# FOC_Explore.net
KiCad netlist of a schematic drawn in EasyEDA Pro
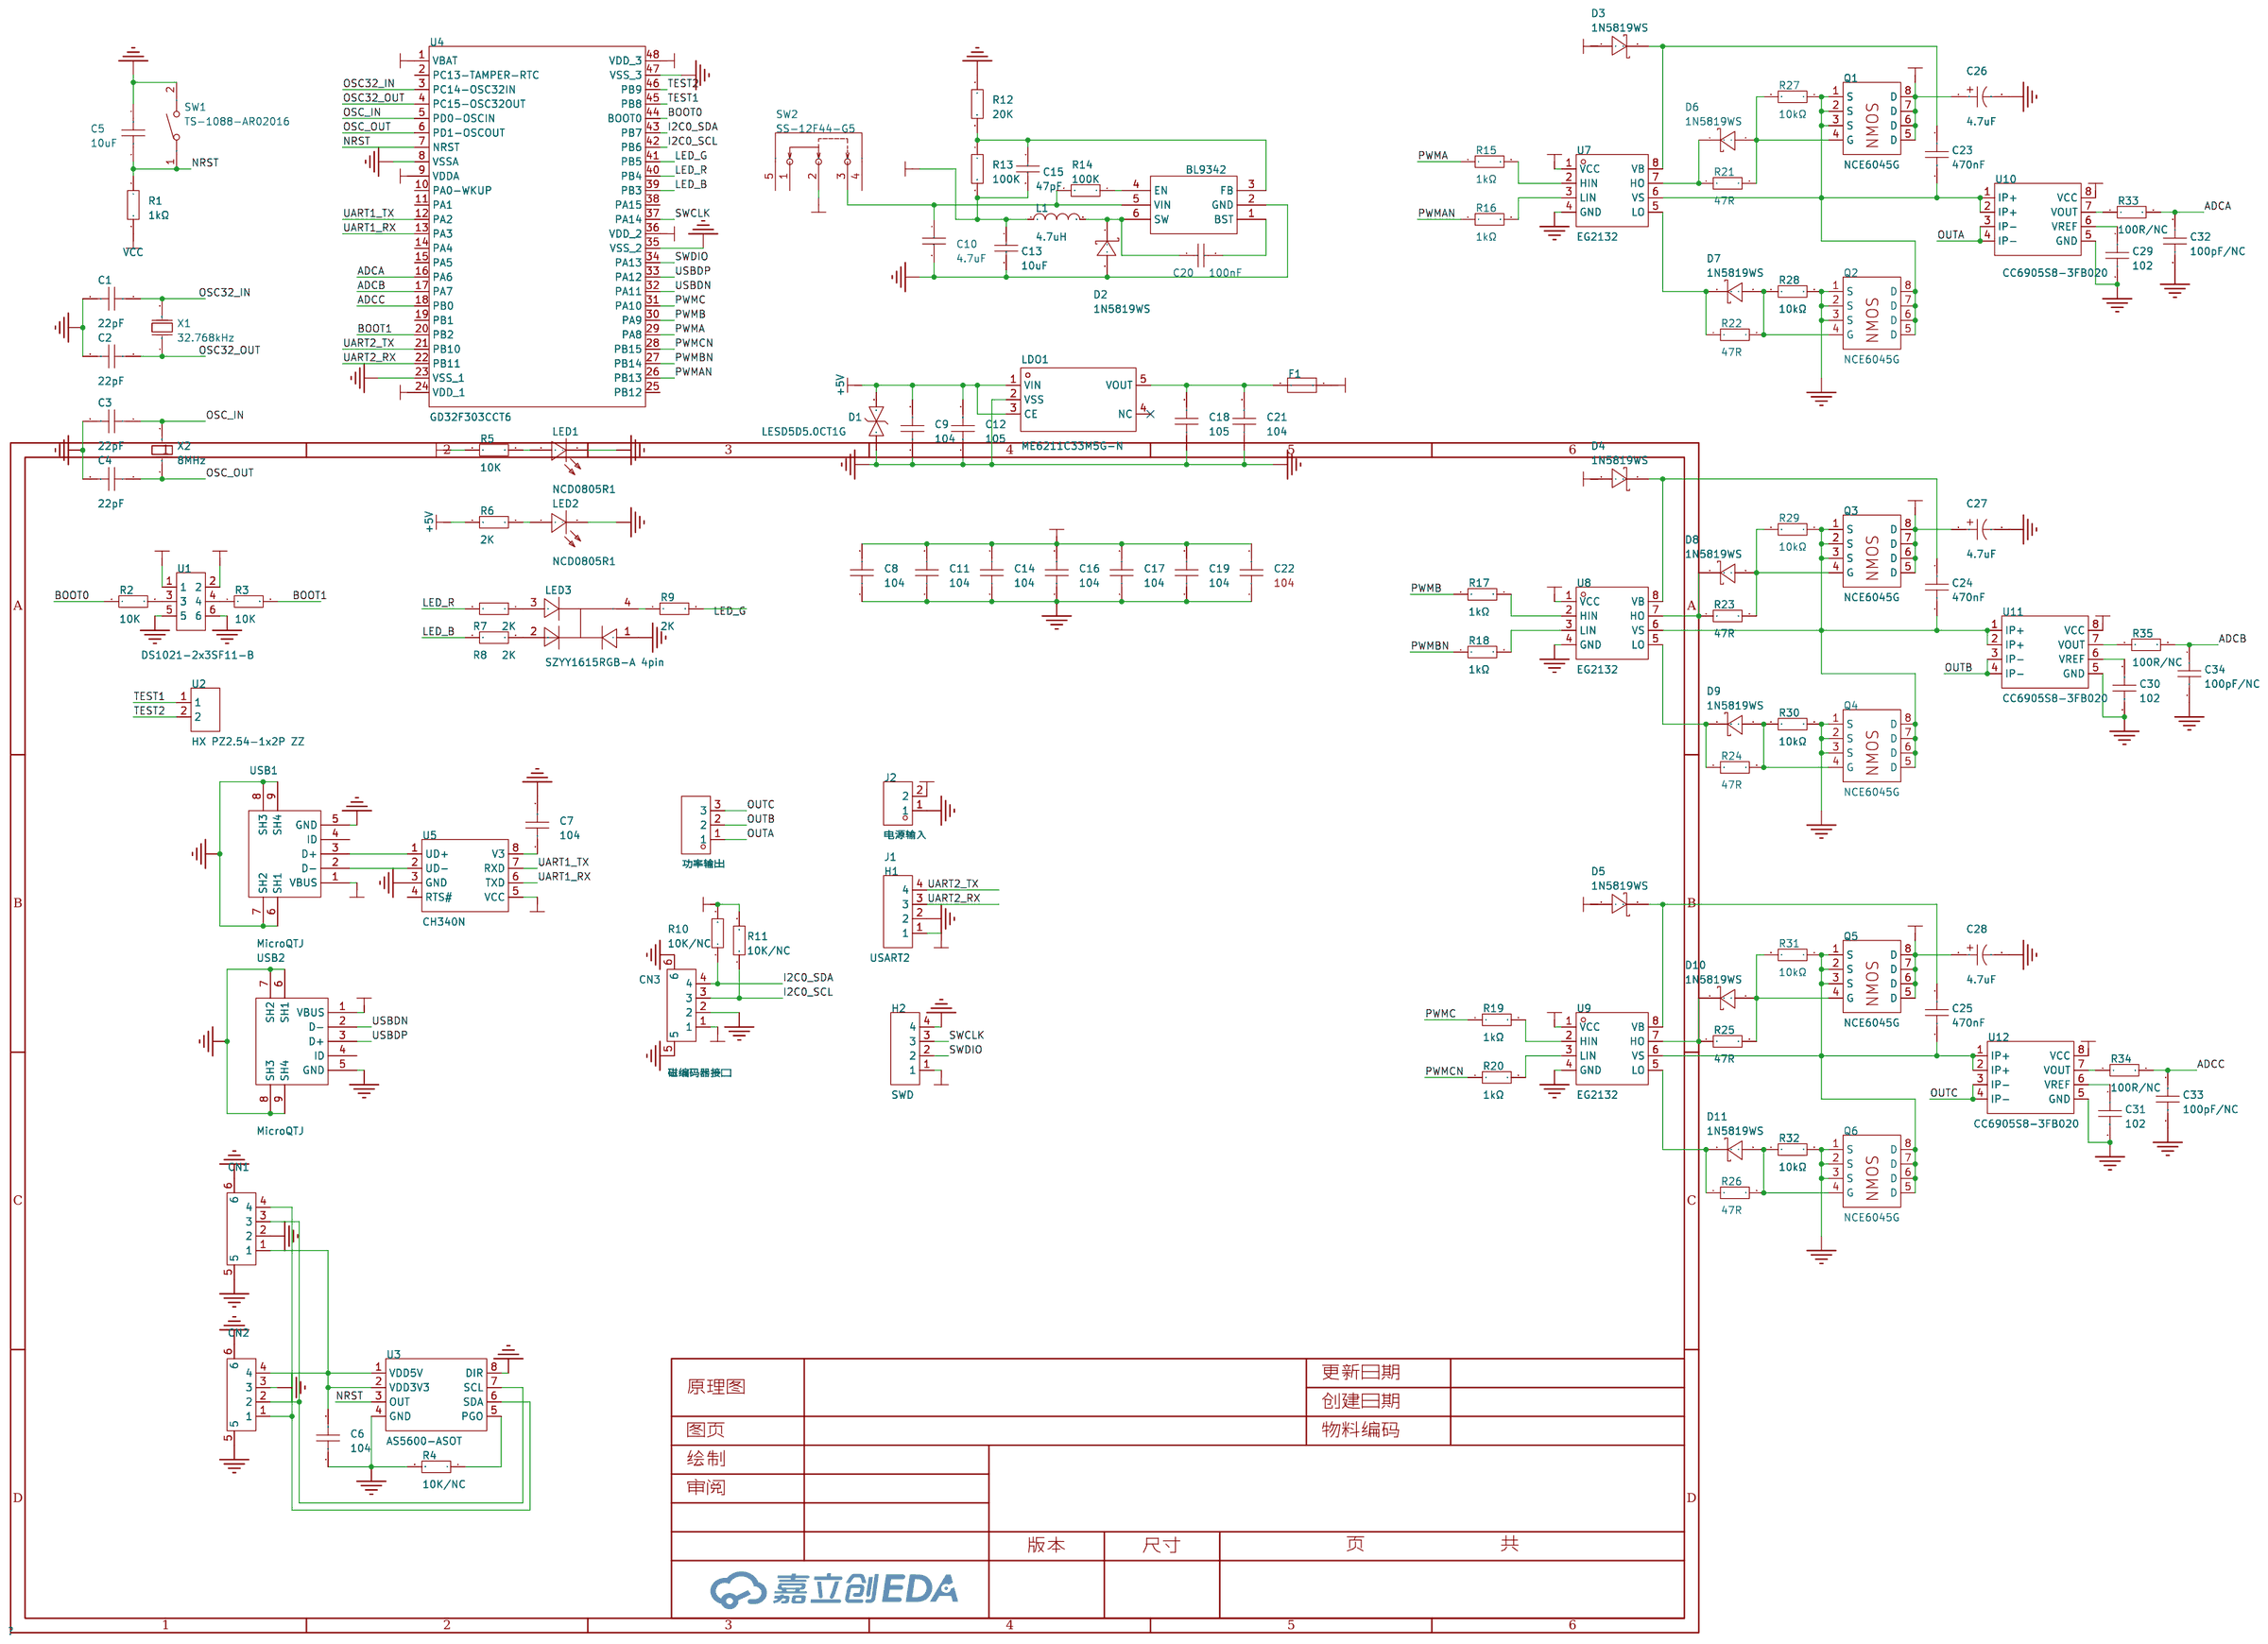
[diagram p0: schematic sheet]

(export (version "E")
  (design (tool "Eeschema 10.0.6"))
  (components
    (comp (ref "C1")
      (value "22pF")
      (footprint "easyedapro:C0805")
      (fields (field (name "Manufacturer") "FH(风华)"))
      (libsource (lib "easyedapro") (part "0805DS106K250NT"))
    )
    (comp (ref "C2")
      (value "22pF")
      (footprint "easyedapro:C0805")
      (fields (field (name "Manufacturer") "FH(风华)"))
      (libsource (lib "easyedapro") (part "0805DS106K250NT"))
    )
    (comp (ref "C3")
      (value "22pF")
      (footprint "easyedapro:C0805")
      (fields (field (name "Manufacturer") "FH(风华)"))
      (libsource (lib "easyedapro") (part "0805DS106K250NT"))
    )
    (comp (ref "C4")
      (value "22pF")
      (footprint "easyedapro:C0805")
      (fields (field (name "Manufacturer") "FH(风华)"))
      (libsource (lib "easyedapro") (part "0805DS106K250NT"))
    )
    (comp (ref "C5")
      (value "10uF")
      (footprint "easyedapro:C0805")
      (fields (field (name "Manufacturer") "FH(风华)"))
      (libsource (lib "easyedapro") (part "0805DS106K250NT"))
    )
    (comp (ref "C6")
      (value "104")
      (footprint "easyedapro:C0603")
      (fields (field (name "Manufacturer") "FH(风华)"))
      (libsource (lib "easyedapro") (part "0603DS106M160NT"))
    )
    (comp (ref "C7")
      (value "104")
      (footprint "easyedapro:C0603")
      (fields (field (name "Manufacturer") "FH(风华)"))
      (libsource (lib "easyedapro") (part "0603DS106M160NT"))
    )
    (comp (ref "C8")
      (value "104")
      (footprint "easyedapro:C0603")
      (fields (field (name "Manufacturer") "FH(风华)"))
      (libsource (lib "easyedapro") (part "0603DS106M160NT"))
    )
    (comp (ref "C9")
      (value "104")
      (footprint "easyedapro:C0603")
      (fields (field (name "Manufacturer") "FH(风华)"))
      (libsource (lib "easyedapro") (part "0603DS106M160NT"))
    )
    (comp (ref "C10")
      (value "4.7uF")
      (footprint "easyedapro:C0603")
      (fields
        (field (name "Manufacturer Part") "CL10C330JB8NNNC")
        (field (name "Manufacturer") "SAMSUNG(三星)")
      )
      (libsource (lib "easyedapro") (part "33pF"))
    )
    (comp (ref "C11")
      (value "104")
      (footprint "easyedapro:C0603")
      (fields (field (name "Manufacturer") "FH(风华)"))
      (libsource (lib "easyedapro") (part "0603DS106M160NT"))
    )
    (comp (ref "C12")
      (value "105")
      (footprint "easyedapro:C0603")
      (fields (field (name "Manufacturer") "FH(风华)"))
      (libsource (lib "easyedapro") (part "0603DS106M160NT"))
    )
    (comp (ref "C13")
      (value "10uF")
      (footprint "easyedapro:C0603")
      (fields (field (name "Manufacturer Part") "0603B104K500NT") (field (name "Manufacturer") "FH(风华)"))
      (libsource (lib "easyedapro") (part "100nF"))
    )
    (comp (ref "C14")
      (value "104")
      (footprint "easyedapro:C0603")
      (fields (field (name "Manufacturer") "FH(风华)"))
      (libsource (lib "easyedapro") (part "0603DS106M160NT"))
    )
    (comp (ref "C15")
      (value "47pF")
      (footprint "easyedapro:C0603")
      (fields (field (name "Manufacturer Part") "0603B104K500NT") (field (name "Manufacturer") "FH(风华)"))
      (libsource (lib "easyedapro") (part "100nF"))
    )
    (comp (ref "C16")
      (value "104")
      (footprint "easyedapro:C0603")
      (fields (field (name "Manufacturer") "FH(风华)"))
      (libsource (lib "easyedapro") (part "0603DS106M160NT"))
    )
    (comp (ref "C17")
      (value "104")
      (footprint "easyedapro:C0603")
      (fields (field (name "Manufacturer") "FH(风华)"))
      (libsource (lib "easyedapro") (part "0603DS106M160NT"))
    )
    (comp (ref "C18")
      (value "105")
      (footprint "easyedapro:C0603")
      (fields (field (name "Manufacturer") "FH(风华)"))
      (libsource (lib "easyedapro") (part "0603DS106M160NT"))
    )
    (comp (ref "C19")
      (value "104")
      (footprint "easyedapro:C0603")
      (fields (field (name "Manufacturer") "FH(风华)"))
      (libsource (lib "easyedapro") (part "0603DS106M160NT"))
    )
    (comp (ref "C20")
      (value "100nF")
      (footprint "easyedapro:C0603")
      (fields (field (name "Manufacturer Part") "0603B104K500NT") (field (name "Manufacturer") "FH(风华)"))
      (libsource (lib "easyedapro") (part "100nF"))
    )
    (comp (ref "C21")
      (value "104")
      (footprint "easyedapro:C0603")
      (fields (field (name "Manufacturer") "FH(风华)"))
      (libsource (lib "easyedapro") (part "0603DS106M160NT"))
    )
    (comp (ref "C22")
      (value "104")
      (footprint "easyedapro:C0603")
      (fields (field (name "Manufacturer Part") "104") (field (name "Manufacturer") "FH(风华)"))
      (libsource (lib "easyedapro") (part "0603DS106M160NT"))
    )
    (comp (ref "C23")
      (value "470nF")
      (footprint "easyedapro:C0805")
      (fields (field (name "Manufacturer") "FH(风华)"))
      (libsource (lib "easyedapro") (part "0805DS106K250NT"))
    )
    (comp (ref "C24")
      (value "470nF")
      (footprint "easyedapro:C0805")
      (fields (field (name "Manufacturer") "FH(风华)"))
      (libsource (lib "easyedapro") (part "0805DS106K250NT"))
    )
    (comp (ref "C25")
      (value "470nF")
      (footprint "easyedapro:C0805")
      (fields (field (name "Manufacturer") "FH(风华)"))
      (libsource (lib "easyedapro") (part "0805DS106K250NT"))
    )
    (comp (ref "C26")
      (value "4.7uF")
      (footprint "easyedapro:CAP-SMD_L3.5-W2.8-FD")
      (description "容值:4.7uF;精度:±10%;额定电压:25V;等效串联电阻(ESR):6Ω@120kHz;")
      (fields (field (name "Manufacturer Part") "178MU0017") (field (name "Manufacturer") "KNSCHA(科尼盛)"))
      (libsource (lib "easyedapro") (part "178MU0017"))
    )
    (comp (ref "C27")
      (value "4.7uF")
      (footprint "easyedapro:CAP-SMD_L3.5-W2.8-FD")
      (description "容值:4.7uF;精度:±10%;额定电压:25V;等效串联电阻(ESR):6Ω@120kHz;")
      (fields (field (name "Manufacturer Part") "178MU0017") (field (name "Manufacturer") "KNSCHA(科尼盛)"))
      (libsource (lib "easyedapro") (part "178MU0017"))
    )
    (comp (ref "C28")
      (value "4.7uF")
      (footprint "easyedapro:CAP-SMD_L3.5-W2.8-FD")
      (description "容值:4.7uF;精度:±10%;额定电压:25V;等效串联电阻(ESR):6Ω@120kHz;")
      (fields (field (name "Manufacturer Part") "178MU0017") (field (name "Manufacturer") "KNSCHA(科尼盛)"))
      (libsource (lib "easyedapro") (part "178MU0017"))
    )
    (comp (ref "C29")
      (value "102")
      (footprint "easyedapro:C0805")
      (fields (field (name "Manufacturer") "FH(风华)"))
      (libsource (lib "easyedapro") (part "0805DS106K250NT"))
    )
    (comp (ref "C30")
      (value "102")
      (footprint "easyedapro:C0805")
      (fields (field (name "Manufacturer") "FH(风华)"))
      (libsource (lib "easyedapro") (part "0805DS106K250NT"))
    )
    (comp (ref "C31")
      (value "102")
      (footprint "easyedapro:C0805")
      (fields (field (name "Manufacturer") "FH(风华)"))
      (libsource (lib "easyedapro") (part "0805DS106K250NT"))
    )
    (comp (ref "C32")
      (value "100pF/NC")
      (footprint "easyedapro:C0805")
      (fields (field (name "Manufacturer") "FH(风华)"))
      (libsource (lib "easyedapro") (part "0805DS106K250NT"))
    )
    (comp (ref "C33")
      (value "100pF/NC")
      (footprint "easyedapro:C0805")
      (fields (field (name "Manufacturer") "FH(风华)"))
      (libsource (lib "easyedapro") (part "0805DS106K250NT"))
    )
    (comp (ref "C34")
      (value "100pF/NC")
      (footprint "easyedapro:C0805")
      (fields (field (name "Manufacturer") "FH(风华)"))
      (libsource (lib "easyedapro") (part "0805DS106K250NT"))
    )
    (comp (ref "CN1")
      (value "HX SH-1.0-4PWT")
      (footprint "easyedapro:CONN-SMD_4P-HX-SH-1.0-4PWT")
      (fields (field (name "Manufacturer") "hanxia(韩下)"))
      (libsource (lib "easyedapro") (part "HX SH-1.0-4PWT"))
    )
    (comp (ref "CN2")
      (value "HX SH-1.0-4PWT")
      (footprint "easyedapro:CONN-SMD_4P-HX-SH-1.0-4PWT")
      (fields (field (name "Manufacturer") "hanxia(韩下)"))
      (libsource (lib "easyedapro") (part "HX SH-1.0-4PWT"))
    )
    (comp (ref "CN3")
      (value "磁编码器接口")
      (footprint "easyedapro:CONN-SMD_4P-HX-SH-1.0-4PWT")
      (fields (field (name "Manufacturer") "hanxia(韩下)"))
      (libsource (lib "easyedapro") (part "HX SH-1.0-4PWT"))
    )
    (comp (ref "D1")
      (value "LESD5D5.0CT1G")
      (footprint "easyedapro:SOD-523_L1.2-W0.8-LS1.6-BI")
      (description "极性:-;反向截止电压(Vrwm):5V;钳位电压:15V;峰值脉冲电流(Ipp):5A;峰值脉冲功率(Ppp):75W;击穿电压:9V;")
      (fields (field (name "Manufacturer") "KUU"))
      (libsource (lib "easyedapro") (part "LESD5D5.0CT1G_C7433850"))
    )
    (comp (ref "D2")
      (value "1N5819WS")
      (footprint "easyedapro:SOD-323_L1.8-W1.3-LS2.5-RD")
      (description "正向压降(Vf):600mV@1A;直流反向耐压(Vr):40V;整流电流:1A;")
      (fields (field (name "Manufacturer") "Hottech(合科泰)"))
      (libsource (lib "easyedapro") (part "1N5819WS"))
    )
    (comp (ref "D3")
      (value "1N5819WS")
      (fields (field (name "Manufacturer") "Hottech(合科泰)"))
      (libsource (lib "easyedapro") (part "1N5819WS"))
    )
    (comp (ref "D4")
      (value "1N5819WS")
      (fields (field (name "Manufacturer") "Hottech(合科泰)"))
      (libsource (lib "easyedapro") (part "1N5819WS"))
    )
    (comp (ref "D5")
      (value "1N5819WS")
      (fields (field (name "Manufacturer") "Hottech(合科泰)"))
      (libsource (lib "easyedapro") (part "1N5819WS"))
    )
    (comp (ref "D6")
      (value "1N5819WS")
      (fields (field (name "Manufacturer") "Hottech(合科泰)"))
      (libsource (lib "easyedapro") (part "1N5819WS"))
    )
    (comp (ref "D7")
      (value "1N5819WS")
      (fields (field (name "Manufacturer") "Hottech(合科泰)"))
      (libsource (lib "easyedapro") (part "1N5819WS"))
    )
    (comp (ref "D8")
      (value "1N5819WS")
      (fields (field (name "Manufacturer") "Hottech(合科泰)"))
      (libsource (lib "easyedapro") (part "1N5819WS"))
    )
    (comp (ref "D9")
      (value "1N5819WS")
      (fields (field (name "Manufacturer") "Hottech(合科泰)"))
      (libsource (lib "easyedapro") (part "1N5819WS"))
    )
    (comp (ref "D10")
      (value "1N5819WS")
      (fields (field (name "Manufacturer") "Hottech(合科泰)"))
      (libsource (lib "easyedapro") (part "1N5819WS"))
    )
    (comp (ref "D11")
      (value "1N5819WS")
      (fields (field (name "Manufacturer") "Hottech(合科泰)"))
      (libsource (lib "easyedapro") (part "1N5819WS"))
    )
    (comp (ref "F1")
      (value "JK-SMD0603-002-30")
      (footprint "easyedapro:F0603")
      (fields (field (name "Manufacturer") "JK(金科)"))
      (libsource (lib "easyedapro") (part "JK-SMD0603-002-30"))
    )
    (comp (ref "H1")
      (value "USART2")
      (footprint "easyedapro:HDR-TH_A254UP-ZD04P")
      (fields (field (name "Manufacturer") "BXCONN(宝讯)"))
      (libsource (lib "easyedapro") (part "A254UP-ZD04P"))
    )
    (comp (ref "H2")
      (value "SWD")
      (footprint "easyedapro:HDR-TH_A254UP-ZD04P")
      (fields (field (name "Manufacturer") "BXCONN(宝讯)"))
      (libsource (lib "easyedapro") (part "A254UP-ZD04P"))
    )
    (comp (ref "J1")
      (value "功率输出")
      (footprint "easyedapro:CONN-TH_XY300V-A-5.0-3P")
      (fields (field (name "Manufacturer") "XINLAIYA(新莱亚)"))
      (libsource (lib "easyedapro") (part "XY300V-A-5.0-3P"))
    )
    (comp (ref "J2")
      (value "电源输入")
      (footprint "easyedapro:CONN-TH_XY301V-A-5.0-2P")
      (description "结构:1x2P;间距:5mm;颜色:蓝色;安装方式:直插;排数:1;每排PIN数:2;额定电流:15A;额定电压:300V;线规 - AWG:14~22;线规 - 平方毫米:1.5;工作温度:-;")
      (fields (field (name "Manufacturer") "XINLAIYA(新莱亚)"))
      (libsource (lib "easyedapro") (part "XY301V-A-5.0-2P"))
    )
    (comp (ref "L1")
      (value "4.7uH")
      (footprint "easyedapro:IND-SMD_L4.4-W4.2")
      (description "电感值:4.7uH;精度:±20%;额定电流:2.8A;饱和电流(Isat):3A;类型:一体成型电感;")
      (fields (field (name "Manufacturer Part") "XR0420-4R7M") (field (name "Manufacturer") "XR(祥如)"))
      (libsource (lib "easyedapro") (part "XR0420-4R7M"))
    )
    (comp (ref "LDO1")
      (value "ME6211C33M5G-N")
      (footprint "easyedapro:SOT-23-5_L3.0-W1.7-P0.95-LS2.8-BL")
      (description "输出类型:固定;最大输入电压:6V;输出电压:3.3V;最大输出电流:500mA;电源纹波抑制比(PSRR):70dB;输出极性:正极;")
      (fields (field (name "Manufacturer") "MICRONE(南京微盟)"))
      (libsource (lib "easyedapro") (part "ME6211C33M5G-N"))
    )
    (comp (ref "LED1")
      (value "NCD0805R1")
      (footprint "easyedapro:LED0805-R-RD")
      (fields (field (name "Manufacturer") "国星光电"))
      (libsource (lib "easyedapro") (part "FC-2012HRK-620D"))
    )
    (comp (ref "LED2")
      (value "NCD0805R1")
      (footprint "easyedapro:LED0805-R-RD")
      (fields (field (name "Manufacturer") "国星光电"))
      (libsource (lib "easyedapro") (part "FC-2012HRK-620D"))
    )
    (comp (ref "LED3")
      (value "SZYY1615RGB-A 4pin")
      (footprint "easyedapro:LED-ARRAY-SMD_4P-L1.6-W1.5_SZYY1615RGB-A")
      (fields (field (name "Manufacturer") "yongyu(永裕光电)"))
      (libsource (lib "easyedapro") (part "SZYY1615RGB-A 4PIN"))
    )
    (comp (ref "Q1")
      (value "NCE6045G")
      (footprint "easyedapro:DFN-8_L5.8-W4.9-P1.27-LS6.1-BL-2")
      (fields (field (name "Manufacturer") "NCE(无锡新洁能)"))
      (libsource (lib "easyedapro") (part "NCE6045G"))
    )
    (comp (ref "Q2")
      (value "NCE6045G")
      (footprint "easyedapro:DFN-8_L5.8-W4.9-P1.27-LS6.1-BL-2")
      (fields (field (name "Manufacturer") "NCE(无锡新洁能)"))
      (libsource (lib "easyedapro") (part "NCE6045G"))
    )
    (comp (ref "Q3")
      (value "NCE6045G")
      (footprint "easyedapro:DFN-8_L5.8-W4.9-P1.27-LS6.1-BL-2")
      (fields (field (name "Manufacturer") "NCE(无锡新洁能)"))
      (libsource (lib "easyedapro") (part "NCE6045G"))
    )
    (comp (ref "Q4")
      (value "NCE6045G")
      (footprint "easyedapro:DFN-8_L5.8-W4.9-P1.27-LS6.1-BL-2")
      (fields (field (name "Manufacturer") "NCE(无锡新洁能)"))
      (libsource (lib "easyedapro") (part "NCE6045G"))
    )
    (comp (ref "Q5")
      (value "NCE6045G")
      (footprint "easyedapro:DFN-8_L5.8-W4.9-P1.27-LS6.1-BL-2")
      (fields (field (name "Manufacturer") "NCE(无锡新洁能)"))
      (libsource (lib "easyedapro") (part "NCE6045G"))
    )
    (comp (ref "Q6")
      (value "NCE6045G")
      (footprint "easyedapro:DFN-8_L5.8-W4.9-P1.27-LS6.1-BL-2")
      (fields (field (name "Manufacturer") "NCE(无锡新洁能)"))
      (libsource (lib "easyedapro") (part "NCE6045G"))
    )
    (comp (ref "R1")
      (value "1kΩ")
      (footprint "easyedapro:R0603")
      (description "电阻类型:厚膜电阻;阻值:1kΩ;精度:±1%;功率:100mW;最大工作电压:75V;温度系数:±100ppm/°C;")
      (fields
        (field (name "Manufacturer Part") "0603WAF1001T5E")
        (field (name "Manufacturer") "UNI-ROYAL(厚声)")
      )
      (libsource (lib "easyedapro") (part "0603WAF1001T5E"))
    )
    (comp (ref "R2")
      (value "10K")
      (footprint "easyedapro:R0603")
      (description "电阻类型:薄膜电阻;阻值:100kΩ;精度:±0.1%;功率:100mW;最大工作电压:75V;温度系数:±25ppm/°C;")
      (fields (field (name "Manufacturer Part") "RT0603BRD07100KL") (field (name "Manufacturer") "YAGEO(国巨)"))
      (libsource (lib "easyedapro") (part "RT0603BRD07100KL"))
    )
    (comp (ref "R3")
      (value "10K")
      (footprint "easyedapro:R0603")
      (description "电阻类型:薄膜电阻;阻值:100kΩ;精度:±0.1%;功率:100mW;最大工作电压:75V;温度系数:±25ppm/°C;")
      (fields (field (name "Manufacturer Part") "RT0603BRD07100KL") (field (name "Manufacturer") "YAGEO(国巨)"))
      (libsource (lib "easyedapro") (part "RT0603BRD07100KL"))
    )
    (comp (ref "R4")
      (value "10K/NC")
      (footprint "easyedapro:R0603")
      (description "电阻类型:厚膜电阻;阻值:10Ω;精度:±1%;功率:100mW;最大工作电压:75V;温度系数:±400ppm/°C;")
      (fields
        (field (name "Manufacturer Part") "0603WAF100JT5E")
        (field (name "Manufacturer") "UNI-ROYAL(厚声)")
      )
      (libsource (lib "easyedapro") (part "0603WAF100JT5E"))
    )
    (comp (ref "R5")
      (value "10K")
      (fields (field (name "Manufacturer Part") "RT0603BRE0750RL") (field (name "Manufacturer") "YAGEO(国巨)"))
      (libsource (lib "easyedapro") (part "0603WAF300JT5E"))
    )
    (comp (ref "R6")
      (value "2K")
      (fields (field (name "Manufacturer Part") "RT0603BRE0750RL") (field (name "Manufacturer") "YAGEO(国巨)"))
      (libsource (lib "easyedapro") (part "0603WAF300JT5E"))
    )
    (comp (ref "R7")
      (value "2K")
      (fields (field (name "Manufacturer Part") "RT0603BRE0750RL") (field (name "Manufacturer") "YAGEO(国巨)"))
      (libsource (lib "easyedapro") (part "0603WAF300JT5E"))
    )
    (comp (ref "R8")
      (value "2K")
      (fields (field (name "Manufacturer Part") "RT0603BRE0750RL") (field (name "Manufacturer") "YAGEO(国巨)"))
      (libsource (lib "easyedapro") (part "0603WAF300JT5E"))
    )
    (comp (ref "R9")
      (value "2K")
      (fields (field (name "Manufacturer Part") "RT0603BRE0750RL") (field (name "Manufacturer") "YAGEO(国巨)"))
      (libsource (lib "easyedapro") (part "0603WAF300JT5E"))
    )
    (comp (ref "R10")
      (value "10K/NC")
      (footprint "easyedapro:R0603")
      (description "电阻类型:厚膜电阻;阻值:10Ω;精度:±1%;功率:100mW;最大工作电压:75V;温度系数:±400ppm/°C;")
      (fields
        (field (name "Manufacturer Part") "0603WAF100JT5E")
        (field (name "Manufacturer") "UNI-ROYAL(厚声)")
      )
      (libsource (lib "easyedapro") (part "0603WAF100JT5E"))
    )
    (comp (ref "R11")
      (value "10K/NC")
      (footprint "easyedapro:R0603")
      (description "电阻类型:厚膜电阻;阻值:10Ω;精度:±1%;功率:100mW;最大工作电压:75V;温度系数:±400ppm/°C;")
      (fields
        (field (name "Manufacturer Part") "0603WAF100JT5E")
        (field (name "Manufacturer") "UNI-ROYAL(厚声)")
      )
      (libsource (lib "easyedapro") (part "0603WAF100JT5E"))
    )
    (comp (ref "R12")
      (value "20K")
      (footprint "easyedapro:R0603")
      (fields
        (field (name "Manufacturer Part") "0603WAF2202T5E")
        (field (name "Manufacturer") "UNI-ROYAL(厚声)")
      )
      (libsource (lib "easyedapro") (part "22kΩ"))
    )
    (comp (ref "R13")
      (value "100K")
      (footprint "easyedapro:R0603")
      (fields
        (field (name "Manufacturer Part") "0603WAF1303T5E")
        (field (name "Manufacturer") "UNI-ROYAL(厚声)")
      )
      (libsource (lib "easyedapro") (part "130kΩ"))
    )
    (comp (ref "R14")
      (value "100K")
      (footprint "easyedapro:R0603")
      (fields
        (field (name "Manufacturer Part") "0603WAF1243T5E")
        (field (name "Manufacturer") "UNI-ROYAL(厚声)")
      )
      (libsource (lib "easyedapro") (part "124kΩ"))
    )
    (comp (ref "R15")
      (value "1kΩ")
      (footprint "easyedapro:R0603")
      (description "电阻类型:厚膜电阻;阻值:10kΩ;精度:±1%;功率:100mW;最大工作电压:75V;温度系数:±100ppm/°C;")
      (fields
        (field (name "Manufacturer Part") "0603WAF1002T5E")
        (field (name "Manufacturer") "UNI-ROYAL(厚声)")
      )
      (libsource (lib "easyedapro") (part "0603WAF1002T5E"))
    )
    (comp (ref "R16")
      (value "1kΩ")
      (footprint "easyedapro:R0603")
      (description "电阻类型:厚膜电阻;阻值:10kΩ;精度:±1%;功率:100mW;最大工作电压:75V;温度系数:±100ppm/°C;")
      (fields
        (field (name "Manufacturer Part") "0603WAF1002T5E")
        (field (name "Manufacturer") "UNI-ROYAL(厚声)")
      )
      (libsource (lib "easyedapro") (part "0603WAF1002T5E"))
    )
    (comp (ref "R17")
      (value "1kΩ")
      (footprint "easyedapro:R0603")
      (description "电阻类型:厚膜电阻;阻值:10kΩ;精度:±1%;功率:100mW;最大工作电压:75V;温度系数:±100ppm/°C;")
      (fields
        (field (name "Manufacturer Part") "0603WAF1002T5E")
        (field (name "Manufacturer") "UNI-ROYAL(厚声)")
      )
      (libsource (lib "easyedapro") (part "0603WAF1002T5E"))
    )
    (comp (ref "R18")
      (value "1kΩ")
      (footprint "easyedapro:R0603")
      (description "电阻类型:厚膜电阻;阻值:10kΩ;精度:±1%;功率:100mW;最大工作电压:75V;温度系数:±100ppm/°C;")
      (fields
        (field (name "Manufacturer Part") "0603WAF1002T5E")
        (field (name "Manufacturer") "UNI-ROYAL(厚声)")
      )
      (libsource (lib "easyedapro") (part "0603WAF1002T5E"))
    )
    (comp (ref "R19")
      (value "1kΩ")
      (footprint "easyedapro:R0603")
      (description "电阻类型:厚膜电阻;阻值:10kΩ;精度:±1%;功率:100mW;最大工作电压:75V;温度系数:±100ppm/°C;")
      (fields
        (field (name "Manufacturer Part") "0603WAF1002T5E")
        (field (name "Manufacturer") "UNI-ROYAL(厚声)")
      )
      (libsource (lib "easyedapro") (part "0603WAF1002T5E"))
    )
    (comp (ref "R20")
      (value "1kΩ")
      (footprint "easyedapro:R0603")
      (description "电阻类型:厚膜电阻;阻值:10kΩ;精度:±1%;功率:100mW;最大工作电压:75V;温度系数:±100ppm/°C;")
      (fields
        (field (name "Manufacturer Part") "0603WAF1002T5E")
        (field (name "Manufacturer") "UNI-ROYAL(厚声)")
      )
      (libsource (lib "easyedapro") (part "0603WAF1002T5E"))
    )
    (comp (ref "R21")
      (value "47R")
      (footprint "easyedapro:R0603")
      (description "电阻类型:厚膜电阻;阻值:10Ω;精度:±1%;功率:100mW;最大工作电压:75V;温度系数:±400ppm/°C;")
      (fields
        (field (name "Manufacturer Part") "0603WAF100JT5E")
        (field (name "Manufacturer") "UNI-ROYAL(厚声)")
      )
      (libsource (lib "easyedapro") (part "0603WAF100JT5E"))
    )
    (comp (ref "R22")
      (value "47R")
      (footprint "easyedapro:R0603")
      (description "电阻类型:厚膜电阻;阻值:10Ω;精度:±1%;功率:100mW;最大工作电压:75V;温度系数:±400ppm/°C;")
      (fields
        (field (name "Manufacturer Part") "0603WAF100JT5E")
        (field (name "Manufacturer") "UNI-ROYAL(厚声)")
      )
      (libsource (lib "easyedapro") (part "0603WAF100JT5E"))
    )
    (comp (ref "R23")
      (value "47R")
      (footprint "easyedapro:R0603")
      (description "电阻类型:厚膜电阻;阻值:10Ω;精度:±1%;功率:100mW;最大工作电压:75V;温度系数:±400ppm/°C;")
      (fields
        (field (name "Manufacturer Part") "0603WAF100JT5E")
        (field (name "Manufacturer") "UNI-ROYAL(厚声)")
      )
      (libsource (lib "easyedapro") (part "0603WAF100JT5E"))
    )
    (comp (ref "R24")
      (value "47R")
      (footprint "easyedapro:R0603")
      (description "电阻类型:厚膜电阻;阻值:10Ω;精度:±1%;功率:100mW;最大工作电压:75V;温度系数:±400ppm/°C;")
      (fields
        (field (name "Manufacturer Part") "0603WAF100JT5E")
        (field (name "Manufacturer") "UNI-ROYAL(厚声)")
      )
      (libsource (lib "easyedapro") (part "0603WAF100JT5E"))
    )
    (comp (ref "R25")
      (value "47R")
      (footprint "easyedapro:R0603")
      (description "电阻类型:厚膜电阻;阻值:10Ω;精度:±1%;功率:100mW;最大工作电压:75V;温度系数:±400ppm/°C;")
      (fields
        (field (name "Manufacturer Part") "0603WAF100JT5E")
        (field (name "Manufacturer") "UNI-ROYAL(厚声)")
      )
      (libsource (lib "easyedapro") (part "0603WAF100JT5E"))
    )
    (comp (ref "R26")
      (value "47R")
      (footprint "easyedapro:R0603")
      (description "电阻类型:厚膜电阻;阻值:10Ω;精度:±1%;功率:100mW;最大工作电压:75V;温度系数:±400ppm/°C;")
      (fields
        (field (name "Manufacturer Part") "0603WAF100JT5E")
        (field (name "Manufacturer") "UNI-ROYAL(厚声)")
      )
      (libsource (lib "easyedapro") (part "0603WAF100JT5E"))
    )
    (comp (ref "R27")
      (value "10kΩ")
      (footprint "easyedapro:R0603")
      (description "电阻类型:厚膜电阻;阻值:10kΩ;精度:±1%;功率:100mW;最大工作电压:75V;温度系数:±100ppm/°C;")
      (fields
        (field (name "Manufacturer Part") "0603WAF1002T5E")
        (field (name "Manufacturer") "UNI-ROYAL(厚声)")
      )
      (libsource (lib "easyedapro") (part "0603WAF1002T5E"))
    )
    (comp (ref "R28")
      (value "10kΩ")
      (footprint "easyedapro:R0603")
      (description "电阻类型:厚膜电阻;阻值:10kΩ;精度:±1%;功率:100mW;最大工作电压:75V;温度系数:±100ppm/°C;")
      (fields
        (field (name "Manufacturer Part") "0603WAF1002T5E")
        (field (name "Manufacturer") "UNI-ROYAL(厚声)")
      )
      (libsource (lib "easyedapro") (part "0603WAF1002T5E"))
    )
    (comp (ref "R29")
      (value "10kΩ")
      (footprint "easyedapro:R0603")
      (description "电阻类型:厚膜电阻;阻值:10kΩ;精度:±1%;功率:100mW;最大工作电压:75V;温度系数:±100ppm/°C;")
      (fields
        (field (name "Manufacturer Part") "0603WAF1002T5E")
        (field (name "Manufacturer") "UNI-ROYAL(厚声)")
      )
      (libsource (lib "easyedapro") (part "0603WAF1002T5E"))
    )
    (comp (ref "R30")
      (value "10kΩ")
      (footprint "easyedapro:R0603")
      (description "电阻类型:厚膜电阻;阻值:10kΩ;精度:±1%;功率:100mW;最大工作电压:75V;温度系数:±100ppm/°C;")
      (fields
        (field (name "Manufacturer Part") "0603WAF1002T5E")
        (field (name "Manufacturer") "UNI-ROYAL(厚声)")
      )
      (libsource (lib "easyedapro") (part "0603WAF1002T5E"))
    )
    (comp (ref "R31")
      (value "10kΩ")
      (footprint "easyedapro:R0603")
      (description "电阻类型:厚膜电阻;阻值:10kΩ;精度:±1%;功率:100mW;最大工作电压:75V;温度系数:±100ppm/°C;")
      (fields
        (field (name "Manufacturer Part") "0603WAF1002T5E")
        (field (name "Manufacturer") "UNI-ROYAL(厚声)")
      )
      (libsource (lib "easyedapro") (part "0603WAF1002T5E"))
    )
    (comp (ref "R32")
      (value "10kΩ")
      (footprint "easyedapro:R0603")
      (description "电阻类型:厚膜电阻;阻值:10kΩ;精度:±1%;功率:100mW;最大工作电压:75V;温度系数:±100ppm/°C;")
      (fields
        (field (name "Manufacturer Part") "0603WAF1002T5E")
        (field (name "Manufacturer") "UNI-ROYAL(厚声)")
      )
      (libsource (lib "easyedapro") (part "0603WAF1002T5E"))
    )
    (comp (ref "R33")
      (value "100R/NC")
      (footprint "easyedapro:R0603")
      (description "电阻类型:厚膜电阻;阻值:10kΩ;精度:±1%;功率:100mW;最大工作电压:75V;温度系数:±100ppm/°C;")
      (fields
        (field (name "Manufacturer Part") "0603WAF1002T5E")
        (field (name "Manufacturer") "UNI-ROYAL(厚声)")
      )
      (libsource (lib "easyedapro") (part "0603WAF1002T5E"))
    )
    (comp (ref "R34")
      (value "100R/NC")
      (footprint "easyedapro:R0603")
      (description "电阻类型:厚膜电阻;阻值:10kΩ;精度:±1%;功率:100mW;最大工作电压:75V;温度系数:±100ppm/°C;")
      (fields
        (field (name "Manufacturer Part") "0603WAF1002T5E")
        (field (name "Manufacturer") "UNI-ROYAL(厚声)")
      )
      (libsource (lib "easyedapro") (part "0603WAF1002T5E"))
    )
    (comp (ref "R35")
      (value "100R/NC")
      (footprint "easyedapro:R0603")
      (description "电阻类型:厚膜电阻;阻值:10kΩ;精度:±1%;功率:100mW;最大工作电压:75V;温度系数:±100ppm/°C;")
      (fields
        (field (name "Manufacturer Part") "0603WAF1002T5E")
        (field (name "Manufacturer") "UNI-ROYAL(厚声)")
      )
      (libsource (lib "easyedapro") (part "0603WAF1002T5E"))
    )
    (comp (ref "SW1")
      (value "TS-1088-AR02016")
      (footprint "easyedapro:SW-SMD_L3.9-W3.0-P4.45")
      (fields (field (name "Manufacturer") "XUNPU(讯普)"))
      (libsource (lib "easyedapro") (part "TS-1088-AR02016"))
    )
    (comp (ref "SW2")
      (value "SS-12F44-G5")
      (footprint "easyedapro:SW-TH_SS-12F44-G5")
      (description "电路结构:单刀双掷;安装方式:直插;额定电流:-;额定电压:-;工作寿命:5千次;")
      (fields (field (name "Manufacturer") "韩国韩荣"))
      (libsource (lib "easyedapro") (part "SS-12F44-G5"))
    )
    (comp (ref "U1")
      (value "DS1021-2x3SF11-B")
      (footprint "easyedapro:HDR-TH_6P-P2.54-V-M-R2-C3-S2.54")
      (fields (field (name "Manufacturer") "CONNFLY"))
      (libsource (lib "easyedapro") (part "DS1021-2X3SF11-B"))
    )
    (comp (ref "U2")
      (value "HX PZ2.54-1x2P ZZ")
      (footprint "easyedapro:HDR-TH_2P-P2.54-V-M-3")
      (fields (field (name "Manufacturer") "hanxia(韩下)"))
      (libsource (lib "easyedapro") (part "HX PZ2.54-1X2P ZZ"))
    )
    (comp (ref "U3")
      (value "AS5600-ASOT")
      (footprint "easyedapro:SOIC-8_L5.0-W4.0-P1.27-LS6.0-BL")
      (description "旋转角度范围:0°~360°;")
      (fields (field (name "Manufacturer") "ams(艾迈斯半导体)"))
      (libsource (lib "easyedapro") (part "AS5600-ASOT"))
    )
    (comp (ref "U4")
      (value "GD32F303CCT6")
      (footprint "easyedapro:LQFP-48_L7.0-W7.0-P0.50-LS9.0-BL")
      (description "CPU内核:ARM Cortex-M4;CPU最大主频:120MHz;")
      (fields (field (name "Manufacturer") "GigaDevice(兆易创新)"))
      (libsource (lib "easyedapro") (part "GD32F303CCT6"))
    )
    (comp (ref "U5")
      (value "CH340N")
      (footprint "easyedapro:SOP-8_L4.9-W3.9-P1.27-LS6.0-BL")
      (description "应用功能:USB转串口;USB协议版本:USB 2.0;通道数:1;数据速率:2Mbps;")
      (fields (field (name "Manufacturer") "WCH(南京沁恒)"))
      (libsource (lib "easyedapro") (part "CH340N_C2977777"))
    )
    (comp (ref "U6")
      (value "BL9342")
      (footprint "easyedapro:SOT-23-6_L2.9-W1.6-P0.95-LS2.8-BL")
      (fields (field (name "Manufacturer") "BL(上海贝岭)"))
      (libsource (lib "easyedapro") (part "BL9342"))
    )
    (comp (ref "U7")
      (value "EG2132")
      (footprint "easyedapro:SOP-8_L4.9-W3.9-P1.27-LS6.0-BL")
      (fields (field (name "Manufacturer") "EG(屹晶微)"))
      (libsource (lib "easyedapro") (part "EG2132"))
    )
    (comp (ref "U8")
      (value "EG2132")
      (footprint "easyedapro:SOP-8_L4.9-W3.9-P1.27-LS6.0-BL")
      (fields (field (name "Manufacturer") "EG(屹晶微)"))
      (libsource (lib "easyedapro") (part "EG2132"))
    )
    (comp (ref "U9")
      (value "EG2132")
      (footprint "easyedapro:SOP-8_L4.9-W3.9-P1.27-LS6.0-BL")
      (fields (field (name "Manufacturer") "EG(屹晶微)"))
      (libsource (lib "easyedapro") (part "EG2132"))
    )
    (comp (ref "U10")
      (value "CC6905S8-3FB020")
      (footprint "easyedapro:SOIC-8_L4.9-W3.9-P1.27-LS6.0-BL")
      (description "电流测量范围:±20A;隔离电压(Vrms):100Vrms;灵敏度:66mV/A;")
      (fields (field (name "Manufacturer") "CrossChip(成都芯进)"))
      (libsource (lib "easyedapro") (part "CC6905S8-3FB020"))
    )
    (comp (ref "U11")
      (value "CC6905S8-3FB020")
      (footprint "easyedapro:SOIC-8_L4.9-W3.9-P1.27-LS6.0-BL")
      (description "电流测量范围:±20A;隔离电压(Vrms):100Vrms;灵敏度:66mV/A;")
      (fields (field (name "Manufacturer") "CrossChip(成都芯进)"))
      (libsource (lib "easyedapro") (part "CC6905S8-3FB020"))
    )
    (comp (ref "U12")
      (value "CC6905S8-3FB020")
      (footprint "easyedapro:SOIC-8_L4.9-W3.9-P1.27-LS6.0-BL")
      (description "电流测量范围:±20A;隔离电压(Vrms):100Vrms;灵敏度:66mV/A;")
      (fields (field (name "Manufacturer") "CrossChip(成都芯进)"))
      (libsource (lib "easyedapro") (part "CC6905S8-3FB020"))
    )
    (comp (ref "USB1")
      (value "MicroQTJ")
      (footprint "easyedapro:MICRO-USB-SMD_MICROQTJ-5P")
      (description "连接器类型:Micro-B;协议标准:USB 2.0;公母:母;安装方式:卧贴;触点数量:5P;端口数量:1;额定电流 - 电源:-;工作温度:-30°C~+80°C;")
      (fields (field (name "Manufacturer") "SHOU HAN(首韩)"))
      (libsource (lib "easyedapro") (part "MICROQTJ"))
    )
    (comp (ref "USB2")
      (value "MicroQTJ")
      (footprint "easyedapro:MICRO-USB-SMD_MICROQTJ-5P")
      (description "连接器类型:Micro-B;协议标准:USB 2.0;公母:母;安装方式:卧贴;触点数量:5P;端口数量:1;额定电流 - 电源:-;工作温度:-30°C~+80°C;")
      (fields (field (name "Manufacturer") "SHOU HAN(首韩)"))
      (libsource (lib "easyedapro") (part "MICROQTJ"))
    )
    (comp (ref "X1")
      (value "32.768kHz")
      (footprint "easyedapro:CRYSTAL-SMD_L3.2-W1.5-1")
      (description "晶振类型:贴片晶振;频率:32.768kHz;常温频差:±20ppm;负载电容:12.5pF;频率稳定度:±30ppm;")
      (fields
        (field (name "Manufacturer Part") "XKXGI-SUA-32.768K")
        (field (name "Manufacturer") "YXC(扬兴晶振)")
      )
      (libsource (lib "easyedapro") (part "XKXGI-SUA-32.768K"))
    )
    (comp (ref "X2")
      (value "8MHz")
      (footprint "easyedapro:CRYSTAL-SMD_L5.0-W3.2")
      (description "晶振类型:贴片晶振;频率:8MHz;常温频差:±10ppm;负载电容:20pF;频率稳定度:±20ppm;")
      (fields
        (field (name "Manufacturer Part") "XG1EL89CSI-111YLC-8M")
        (field (name "Manufacturer") "YXC(扬兴晶振)")
      )
      (libsource (lib "easyedapro") (part "XG1EL89CSI-111YLC-8M"))
    )
  )
  (nets
    (net (code "1") (name "+3V3") (class "Default")
      (node (ref "C11") (pin "2") (pinfunction "2_2") (pintype "unspecified"))
      (node (ref "C14") (pin "2") (pinfunction "2_2") (pintype "unspecified"))
      (node (ref "C16") (pin "2") (pinfunction "2_2") (pintype "unspecified"))
      (node (ref "C17") (pin "2") (pinfunction "2_2") (pintype "unspecified"))
      (node (ref "C19") (pin "2") (pinfunction "2_2") (pintype "unspecified"))
      (node (ref "C22") (pin "2") (pinfunction "2_2") (pintype "unspecified"))
      (node (ref "C8") (pin "2") (pinfunction "2_2") (pintype "unspecified"))
      (node (ref "CN3") (pin "1") (pinfunction "1_1") (pintype "unspecified"))
      (node (ref "F1") (pin "2") (pinfunction "2_2") (pintype "unspecified"))
      (node (ref "H1") (pin "1") (pinfunction "1_1") (pintype "unspecified"))
      (node (ref "H2") (pin "1") (pinfunction "1_1") (pintype "unspecified"))
      (node (ref "R10") (pin "2") (pinfunction "2_2") (pintype "input"))
      (node (ref "R11") (pin "2") (pinfunction "2_2") (pintype "input"))
      (node (ref "U1") (pin "1") (pinfunction "1_1") (pintype "unspecified"))
      (node (ref "U1") (pin "2") (pinfunction "2_2") (pintype "unspecified"))
      (node (ref "U10") (pin "8") (pinfunction "VCC_8") (pintype "unspecified"))
      (node (ref "U11") (pin "8") (pinfunction "VCC_8") (pintype "unspecified"))
      (node (ref "U12") (pin "8") (pinfunction "VCC_8") (pintype "unspecified"))
      (node (ref "U4") (pin "1") (pinfunction "VBAT_1") (pintype "unspecified"))
      (node (ref "U4") (pin "24") (pinfunction "VDD_1_24") (pintype "unspecified"))
      (node (ref "U4") (pin "36") (pinfunction "VDD_2_36") (pintype "unspecified"))
      (node (ref "U4") (pin "48") (pinfunction "VDD_3_48") (pintype "unspecified"))
      (node (ref "U4") (pin "9") (pinfunction "VDDA_9") (pintype "unspecified"))
    )
    (net (code "2") (name "+5V") (class "Default")
      (node (ref "C12") (pin "2") (pinfunction "2_2") (pintype "unspecified"))
      (node (ref "C13") (pin "1") (pinfunction "1_1") (pintype "input"))
      (node (ref "C15") (pin "2") (pinfunction "2_2") (pintype "input"))
      (node (ref "C9") (pin "2") (pinfunction "2_2") (pintype "unspecified"))
      (node (ref "D1") (pin "2") (pinfunction "2_2") (pintype "unspecified"))
      (node (ref "L1") (pin "1") (pinfunction "1_1") (pintype "unspecified"))
      (node (ref "LDO1") (pin "1") (pinfunction "VIN_1") (pintype "unspecified"))
      (node (ref "LDO1") (pin "3") (pinfunction "CE_3") (pintype "unspecified"))
      (node (ref "R13") (pin "2") (pinfunction "2_2") (pintype "input"))
      (node (ref "R6") (pin "2") (pinfunction "2_2") (pintype "input"))
      (node (ref "U5") (pin "5") (pinfunction "VCC_5") (pintype "unspecified"))
      (node (ref "USB1") (pin "1") (pinfunction "VBUS_1") (pintype "unspecified"))
      (node (ref "USB2") (pin "1") (pinfunction "VBUS_1") (pintype "unspecified"))
    )
    (net (code "3") (name "+12V") (class "Default")
      (node (ref "C26") (pin "1") (pinfunction "1_1") (pintype "input"))
      (node (ref "C27") (pin "1") (pinfunction "1_1") (pintype "input"))
      (node (ref "C28") (pin "1") (pinfunction "1_1") (pintype "input"))
      (node (ref "D3") (pin "2") (pinfunction "A_2") (pintype "unspecified"))
      (node (ref "D4") (pin "2") (pinfunction "A_2") (pintype "unspecified"))
      (node (ref "D5") (pin "2") (pinfunction "A_2") (pintype "unspecified"))
      (node (ref "J2") (pin "2") (pinfunction "2_2") (pintype "unspecified"))
      (node (ref "Q1") (pin "5") (pinfunction "D_5") (pintype "unspecified"))
      (node (ref "Q1") (pin "6") (pinfunction "D_6") (pintype "unspecified"))
      (node (ref "Q1") (pin "7") (pinfunction "D_7") (pintype "unspecified"))
      (node (ref "Q1") (pin "8") (pinfunction "D_8") (pintype "unspecified"))
      (node (ref "Q3") (pin "5") (pinfunction "D_5") (pintype "unspecified"))
      (node (ref "Q3") (pin "6") (pinfunction "D_6") (pintype "unspecified"))
      (node (ref "Q3") (pin "7") (pinfunction "D_7") (pintype "unspecified"))
      (node (ref "Q3") (pin "8") (pinfunction "D_8") (pintype "unspecified"))
      (node (ref "Q5") (pin "5") (pinfunction "D_5") (pintype "unspecified"))
      (node (ref "Q5") (pin "6") (pinfunction "D_6") (pintype "unspecified"))
      (node (ref "Q5") (pin "7") (pinfunction "D_7") (pintype "unspecified"))
      (node (ref "Q5") (pin "8") (pinfunction "D_8") (pintype "unspecified"))
      (node (ref "R5") (pin "2") (pinfunction "2_2") (pintype "input"))
      (node (ref "SW2") (pin "2") (pinfunction "2_2") (pintype "unspecified"))
      (node (ref "U7") (pin "1") (pinfunction "VCC_1") (pintype "unspecified"))
      (node (ref "U8") (pin "1") (pinfunction "VCC_1") (pintype "unspecified"))
      (node (ref "U9") (pin "1") (pinfunction "VCC_1") (pintype "unspecified"))
    )
    (net (code "4") (name "/ADCA") (class "Default")
      (node (ref "C32") (pin "1") (pinfunction "1_1") (pintype "unspecified"))
      (node (ref "R33") (pin "2") (pinfunction "2_2") (pintype "input"))
      (node (ref "U4") (pin "16") (pinfunction "PA6_16") (pintype "unspecified"))
    )
    (net (code "5") (name "/ADCB") (class "Default")
      (node (ref "C34") (pin "1") (pinfunction "1_1") (pintype "unspecified"))
      (node (ref "R35") (pin "2") (pinfunction "2_2") (pintype "input"))
      (node (ref "U4") (pin "17") (pinfunction "PA7_17") (pintype "unspecified"))
    )
    (net (code "6") (name "/ADCC") (class "Default")
      (node (ref "C33") (pin "1") (pinfunction "1_1") (pintype "unspecified"))
      (node (ref "R34") (pin "2") (pinfunction "2_2") (pintype "input"))
      (node (ref "U4") (pin "18") (pinfunction "PB0_18") (pintype "unspecified"))
    )
    (net (code "7") (name "/BOOT0") (class "Default")
      (node (ref "R2") (pin "1") (pinfunction "1_1") (pintype "input"))
      (node (ref "U4") (pin "44") (pinfunction "BOOT0_44") (pintype "unspecified"))
    )
    (net (code "8") (name "/BOOT1") (class "Default")
      (node (ref "R3") (pin "2") (pinfunction "2_2") (pintype "input"))
      (node (ref "U4") (pin "20") (pinfunction "PB2_20") (pintype "unspecified"))
    )
    (net (code "9") (name "/I2C0_SCL") (class "Default")
      (node (ref "CN3") (pin "3") (pinfunction "3_3") (pintype "unspecified"))
      (node (ref "R11") (pin "1") (pinfunction "1_1") (pintype "input"))
      (node (ref "U4") (pin "42") (pinfunction "PB6_42") (pintype "unspecified"))
    )
    (net (code "10") (name "/I2C0_SDA") (class "Default")
      (node (ref "CN3") (pin "4") (pinfunction "4_4") (pintype "unspecified"))
      (node (ref "R10") (pin "1") (pinfunction "1_1") (pintype "input"))
      (node (ref "U4") (pin "43") (pinfunction "PB7_43") (pintype "unspecified"))
    )
    (net (code "11") (name "/LED_B") (class "Default")
      (node (ref "R8") (pin "2") (pinfunction "2_2") (pintype "input"))
      (node (ref "U4") (pin "39") (pinfunction "PB3_39") (pintype "unspecified"))
    )
    (net (code "12") (name "/LED_G") (class "Default")
      (node (ref "R9") (pin "2") (pinfunction "2_2") (pintype "input"))
      (node (ref "U4") (pin "41") (pinfunction "PB5_41") (pintype "unspecified"))
    )
    (net (code "13") (name "/LED_R") (class "Default")
      (node (ref "R7") (pin "2") (pinfunction "2_2") (pintype "input"))
      (node (ref "U4") (pin "40") (pinfunction "PB4_40") (pintype "unspecified"))
    )
    (net (code "14") (name "/NRST") (class "Default")
      (node (ref "C5") (pin "2") (pinfunction "2_2") (pintype "unspecified"))
      (node (ref "R1") (pin "1") (pinfunction "1_1") (pintype "input"))
      (node (ref "SW1") (pin "1") (pinfunction "1_1") (pintype "unspecified"))
      (node (ref "U3") (pin "3") (pinfunction "OUT_3") (pintype "unspecified"))
      (node (ref "U4") (pin "7") (pinfunction "NRST_7") (pintype "unspecified"))
    )
    (net (code "15") (name "/OSC32_IN") (class "Default")
      (node (ref "C1") (pin "1") (pinfunction "1_1") (pintype "unspecified"))
      (node (ref "U4") (pin "3") (pinfunction "PC14-OSC32IN_3") (pintype "unspecified"))
      (node (ref "X1") (pin "2") (pinfunction "OSC2_2") (pintype "input"))
    )
    (net (code "16") (name "/OSC32_OUT") (class "Default")
      (node (ref "C2") (pin "1") (pinfunction "1_1") (pintype "unspecified"))
      (node (ref "U4") (pin "4") (pinfunction "PC15-OSC32OUT_4") (pintype "unspecified"))
      (node (ref "X1") (pin "1") (pinfunction "OSC1_1") (pintype "input"))
    )
    (net (code "17") (name "/OSC_IN") (class "Default")
      (node (ref "C3") (pin "1") (pinfunction "1_1") (pintype "unspecified"))
      (node (ref "U4") (pin "5") (pinfunction "PD0-OSCIN_5") (pintype "unspecified"))
      (node (ref "X2") (pin "1") (pinfunction "OSC1_1") (pintype "input"))
    )
    (net (code "18") (name "/OSC_OUT") (class "Default")
      (node (ref "C4") (pin "1") (pinfunction "1_1") (pintype "unspecified"))
      (node (ref "U4") (pin "6") (pinfunction "PD1-OSCOUT_6") (pintype "unspecified"))
      (node (ref "X2") (pin "2") (pinfunction "OSC2_2") (pintype "input"))
    )
    (net (code "19") (name "/OUTA") (class "Default")
      (node (ref "J1") (pin "1") (pinfunction "1_1") (pintype "unspecified"))
      (node (ref "U10") (pin "3") (pinfunction "IP-_3") (pintype "unspecified"))
      (node (ref "U10") (pin "4") (pinfunction "IP-_4") (pintype "unspecified"))
    )
    (net (code "20") (name "/OUTB") (class "Default")
      (node (ref "J1") (pin "2") (pinfunction "2_2") (pintype "unspecified"))
      (node (ref "U11") (pin "3") (pinfunction "IP-_3") (pintype "unspecified"))
      (node (ref "U11") (pin "4") (pinfunction "IP-_4") (pintype "unspecified"))
    )
    (net (code "21") (name "/OUTC") (class "Default")
      (node (ref "J1") (pin "3") (pinfunction "3_3") (pintype "unspecified"))
      (node (ref "U12") (pin "3") (pinfunction "IP-_3") (pintype "unspecified"))
      (node (ref "U12") (pin "4") (pinfunction "IP-_4") (pintype "unspecified"))
    )
    (net (code "22") (name "/PWMA") (class "Default")
      (node (ref "R15") (pin "1") (pinfunction "1_1") (pintype "input"))
      (node (ref "U4") (pin "29") (pinfunction "PA8_29") (pintype "unspecified"))
    )
    (net (code "23") (name "/PWMAN") (class "Default")
      (node (ref "R16") (pin "1") (pinfunction "1_1") (pintype "input"))
      (node (ref "U4") (pin "26") (pinfunction "PB13_26") (pintype "unspecified"))
    )
    (net (code "24") (name "/PWMB") (class "Default")
      (node (ref "R17") (pin "1") (pinfunction "1_1") (pintype "input"))
      (node (ref "U4") (pin "30") (pinfunction "PA9_30") (pintype "unspecified"))
    )
    (net (code "25") (name "/PWMBN") (class "Default")
      (node (ref "R18") (pin "1") (pinfunction "1_1") (pintype "input"))
      (node (ref "U4") (pin "27") (pinfunction "PB14_27") (pintype "unspecified"))
    )
    (net (code "26") (name "/PWMC") (class "Default")
      (node (ref "R19") (pin "1") (pinfunction "1_1") (pintype "input"))
      (node (ref "U4") (pin "31") (pinfunction "PA10_31") (pintype "unspecified"))
    )
    (net (code "27") (name "/PWMCN") (class "Default")
      (node (ref "R20") (pin "1") (pinfunction "1_1") (pintype "input"))
      (node (ref "U4") (pin "28") (pinfunction "PB15_28") (pintype "unspecified"))
    )
    (net (code "28") (name "/SWCLK") (class "Default")
      (node (ref "H2") (pin "3") (pinfunction "3_3") (pintype "unspecified"))
      (node (ref "U4") (pin "37") (pinfunction "PA14_37") (pintype "unspecified"))
    )
    (net (code "29") (name "/SWDIO") (class "Default")
      (node (ref "H2") (pin "2") (pinfunction "2_2") (pintype "unspecified"))
      (node (ref "U4") (pin "34") (pinfunction "PA13_34") (pintype "unspecified"))
    )
    (net (code "30") (name "/TEST1") (class "Default")
      (node (ref "U2") (pin "1") (pinfunction "1_1") (pintype "unspecified"))
      (node (ref "U4") (pin "45") (pinfunction "PB8_45") (pintype "unspecified"))
    )
    (net (code "31") (name "/TEST2") (class "Default")
      (node (ref "U2") (pin "2") (pinfunction "2_2") (pintype "unspecified"))
      (node (ref "U4") (pin "46") (pinfunction "PB9_46") (pintype "unspecified"))
    )
    (net (code "32") (name "/UART1_RX") (class "Default")
      (node (ref "U4") (pin "13") (pinfunction "PA3_13") (pintype "unspecified"))
      (node (ref "U5") (pin "6") (pinfunction "TXD_6") (pintype "unspecified"))
    )
    (net (code "33") (name "/UART1_TX") (class "Default")
      (node (ref "U4") (pin "12") (pinfunction "PA2_12") (pintype "unspecified"))
      (node (ref "U5") (pin "7") (pinfunction "RXD_7") (pintype "unspecified"))
    )
    (net (code "34") (name "/UART2_RX") (class "Default")
      (node (ref "H1") (pin "3") (pinfunction "3_3") (pintype "unspecified"))
      (node (ref "U4") (pin "22") (pinfunction "PB11_22") (pintype "unspecified"))
    )
    (net (code "35") (name "/UART2_TX") (class "Default")
      (node (ref "H1") (pin "4") (pinfunction "4_4") (pintype "unspecified"))
      (node (ref "U4") (pin "21") (pinfunction "PB10_21") (pintype "unspecified"))
    )
    (net (code "36") (name "/USBDN") (class "Default")
      (node (ref "U4") (pin "32") (pinfunction "PA11_32") (pintype "unspecified"))
      (node (ref "USB2") (pin "2") (pinfunction "D-_2") (pintype "unspecified"))
    )
    (net (code "37") (name "/USBDP") (class "Default")
      (node (ref "U4") (pin "33") (pinfunction "PA12_33") (pintype "unspecified"))
      (node (ref "USB2") (pin "3") (pinfunction "D+_3") (pintype "unspecified"))
    )
    (net (code "38") (name "GND") (class "Default")
      (node (ref "C1") (pin "2") (pinfunction "2_2") (pintype "unspecified"))
      (node (ref "C10") (pin "2") (pinfunction "2_2") (pintype "input"))
      (node (ref "C11") (pin "1") (pinfunction "1_1") (pintype "unspecified"))
      (node (ref "C12") (pin "1") (pinfunction "1_1") (pintype "unspecified"))
      (node (ref "C13") (pin "2") (pinfunction "2_2") (pintype "input"))
      (node (ref "C14") (pin "1") (pinfunction "1_1") (pintype "unspecified"))
      (node (ref "C16") (pin "1") (pinfunction "1_1") (pintype "unspecified"))
      (node (ref "C17") (pin "1") (pinfunction "1_1") (pintype "unspecified"))
      (node (ref "C18") (pin "1") (pinfunction "1_1") (pintype "unspecified"))
      (node (ref "C19") (pin "1") (pinfunction "1_1") (pintype "unspecified"))
      (node (ref "C2") (pin "2") (pinfunction "2_2") (pintype "unspecified"))
      (node (ref "C21") (pin "1") (pinfunction "1_1") (pintype "unspecified"))
      (node (ref "C22") (pin "1") (pinfunction "1_1") (pintype "unspecified"))
      (node (ref "C26") (pin "2") (pinfunction "2_2") (pintype "input"))
      (node (ref "C27") (pin "2") (pinfunction "2_2") (pintype "input"))
      (node (ref "C28") (pin "2") (pinfunction "2_2") (pintype "input"))
      (node (ref "C29") (pin "2") (pinfunction "2_2") (pintype "unspecified"))
      (node (ref "C3") (pin "2") (pinfunction "2_2") (pintype "unspecified"))
      (node (ref "C30") (pin "2") (pinfunction "2_2") (pintype "unspecified"))
      (node (ref "C31") (pin "2") (pinfunction "2_2") (pintype "unspecified"))
      (node (ref "C32") (pin "2") (pinfunction "2_2") (pintype "unspecified"))
      (node (ref "C33") (pin "2") (pinfunction "2_2") (pintype "unspecified"))
      (node (ref "C34") (pin "2") (pinfunction "2_2") (pintype "unspecified"))
      (node (ref "C4") (pin "2") (pinfunction "2_2") (pintype "unspecified"))
      (node (ref "C5") (pin "1") (pinfunction "1_1") (pintype "unspecified"))
      (node (ref "C6") (pin "1") (pinfunction "1_1") (pintype "unspecified"))
      (node (ref "C7") (pin "2") (pinfunction "2_2") (pintype "unspecified"))
      (node (ref "C8") (pin "1") (pinfunction "1_1") (pintype "unspecified"))
      (node (ref "C9") (pin "1") (pinfunction "1_1") (pintype "unspecified"))
      (node (ref "CN1") (pin "2") (pinfunction "2_2") (pintype "unspecified"))
      (node (ref "CN1") (pin "5") (pinfunction "5_5") (pintype "unspecified"))
      (node (ref "CN1") (pin "6") (pinfunction "6_6") (pintype "unspecified"))
      (node (ref "CN2") (pin "3") (pinfunction "3_3") (pintype "unspecified"))
      (node (ref "CN2") (pin "5") (pinfunction "5_5") (pintype "unspecified"))
      (node (ref "CN2") (pin "6") (pinfunction "6_6") (pintype "unspecified"))
      (node (ref "CN3") (pin "2") (pinfunction "2_2") (pintype "unspecified"))
      (node (ref "CN3") (pin "5") (pinfunction "5_5") (pintype "unspecified"))
      (node (ref "CN3") (pin "6") (pinfunction "6_6") (pintype "unspecified"))
      (node (ref "D1") (pin "1") (pinfunction "1_1") (pintype "unspecified"))
      (node (ref "D2") (pin "2") (pinfunction "A_2") (pintype "unspecified"))
      (node (ref "H1") (pin "2") (pinfunction "2_2") (pintype "unspecified"))
      (node (ref "H2") (pin "4") (pinfunction "4_4") (pintype "unspecified"))
      (node (ref "J2") (pin "1") (pinfunction "1_1") (pintype "unspecified"))
      (node (ref "LDO1") (pin "2") (pinfunction "VSS_2") (pintype "unspecified"))
      (node (ref "LED1") (pin "2") (pinfunction "-_2") (pintype "unspecified"))
      (node (ref "LED2") (pin "2") (pinfunction "-_2") (pintype "unspecified"))
      (node (ref "LED3") (pin "1") (pinfunction "A_1") (pintype "unspecified"))
      (node (ref "Q2") (pin "1") (pinfunction "S_1") (pintype "unspecified"))
      (node (ref "Q2") (pin "2") (pinfunction "S_2") (pintype "unspecified"))
      (node (ref "Q2") (pin "3") (pinfunction "S_3") (pintype "unspecified"))
      (node (ref "Q4") (pin "1") (pinfunction "S_1") (pintype "unspecified"))
      (node (ref "Q4") (pin "2") (pinfunction "S_2") (pintype "unspecified"))
      (node (ref "Q4") (pin "3") (pinfunction "S_3") (pintype "unspecified"))
      (node (ref "Q6") (pin "1") (pinfunction "S_1") (pintype "unspecified"))
      (node (ref "Q6") (pin "2") (pinfunction "S_2") (pintype "unspecified"))
      (node (ref "Q6") (pin "3") (pinfunction "S_3") (pintype "unspecified"))
      (node (ref "R12") (pin "1") (pinfunction "1_1") (pintype "input"))
      (node (ref "R28") (pin "2") (pinfunction "2_2") (pintype "input"))
      (node (ref "R30") (pin "2") (pinfunction "2_2") (pintype "input"))
      (node (ref "R32") (pin "2") (pinfunction "2_2") (pintype "input"))
      (node (ref "R4") (pin "2") (pinfunction "2_2") (pintype "input"))
      (node (ref "SW1") (pin "2") (pinfunction "2_2") (pintype "unspecified"))
      (node (ref "U1") (pin "5") (pinfunction "5_5") (pintype "unspecified"))
      (node (ref "U1") (pin "6") (pinfunction "6_6") (pintype "unspecified"))
      (node (ref "U10") (pin "5") (pinfunction "GND_5") (pintype "unspecified"))
      (node (ref "U11") (pin "5") (pinfunction "GND_5") (pintype "unspecified"))
      (node (ref "U12") (pin "5") (pinfunction "GND_5") (pintype "unspecified"))
      (node (ref "U3") (pin "4") (pinfunction "GND_4") (pintype "unspecified"))
      (node (ref "U3") (pin "8") (pinfunction "DIR_8") (pintype "unspecified"))
      (node (ref "U4") (pin "23") (pinfunction "VSS_1_23") (pintype "unspecified"))
      (node (ref "U4") (pin "35") (pinfunction "VSS_2_35") (pintype "unspecified"))
      (node (ref "U4") (pin "47") (pinfunction "VSS_3_47") (pintype "unspecified"))
      (node (ref "U4") (pin "8") (pinfunction "VSSA_8") (pintype "unspecified"))
      (node (ref "U5") (pin "3") (pinfunction "GND_3") (pintype "unspecified"))
      (node (ref "U6") (pin "2") (pinfunction "GND_2") (pintype "unspecified"))
      (node (ref "U7") (pin "4") (pinfunction "GND_4") (pintype "unspecified"))
      (node (ref "U8") (pin "4") (pinfunction "GND_4") (pintype "unspecified"))
      (node (ref "U9") (pin "4") (pinfunction "GND_4") (pintype "unspecified"))
      (node (ref "USB1") (pin "5") (pinfunction "GND_5") (pintype "unspecified"))
      (node (ref "USB1") (pin "6") (pinfunction "SH1_6") (pintype "unspecified"))
      (node (ref "USB1") (pin "7") (pinfunction "SH2_7") (pintype "unspecified"))
      (node (ref "USB1") (pin "8") (pinfunction "SH3_8") (pintype "unspecified"))
      (node (ref "USB1") (pin "9") (pinfunction "SH4_9") (pintype "unspecified"))
      (node (ref "USB2") (pin "5") (pinfunction "GND_5") (pintype "unspecified"))
      (node (ref "USB2") (pin "6") (pinfunction "SH1_6") (pintype "unspecified"))
      (node (ref "USB2") (pin "7") (pinfunction "SH2_7") (pintype "unspecified"))
      (node (ref "USB2") (pin "8") (pinfunction "SH3_8") (pintype "unspecified"))
      (node (ref "USB2") (pin "9") (pinfunction "SH4_9") (pintype "unspecified"))
    )
    (net (code "39") (name "Net-(D2-K)") (class "Default")
      (node (ref "C20") (pin "1") (pinfunction "1_1") (pintype "input"))
      (node (ref "D2") (pin "1") (pinfunction "K_1") (pintype "unspecified"))
      (node (ref "L1") (pin "2") (pinfunction "2_2") (pintype "unspecified"))
      (node (ref "U6") (pin "6") (pinfunction "SW_6") (pintype "unspecified"))
    )
    (net (code "40") (name "Net-(D3-K)") (class "Default")
      (node (ref "C23") (pin "1") (pinfunction "1_1") (pintype "unspecified"))
      (node (ref "D3") (pin "1") (pinfunction "K_1") (pintype "unspecified"))
      (node (ref "U7") (pin "8") (pinfunction "VB_8") (pintype "unspecified"))
    )
    (net (code "41") (name "Net-(D4-K)") (class "Default")
      (node (ref "C24") (pin "1") (pinfunction "1_1") (pintype "unspecified"))
      (node (ref "D4") (pin "1") (pinfunction "K_1") (pintype "unspecified"))
      (node (ref "U8") (pin "8") (pinfunction "VB_8") (pintype "unspecified"))
    )
    (net (code "42") (name "Net-(D5-K)") (class "Default")
      (node (ref "C25") (pin "1") (pinfunction "1_1") (pintype "unspecified"))
      (node (ref "D5") (pin "1") (pinfunction "K_1") (pintype "unspecified"))
      (node (ref "U9") (pin "8") (pinfunction "VB_8") (pintype "unspecified"))
    )
    (net (code "43") (name "Net-(D6-A)") (class "Default")
      (node (ref "D6") (pin "2") (pinfunction "A_2") (pintype "unspecified"))
      (node (ref "Q1") (pin "4") (pinfunction "G_4") (pintype "unspecified"))
      (node (ref "R21") (pin "2") (pinfunction "2_2") (pintype "input"))
      (node (ref "R27") (pin "2") (pinfunction "2_2") (pintype "input"))
    )
    (net (code "44") (name "Net-(D6-K)") (class "Default")
      (node (ref "D6") (pin "1") (pinfunction "K_1") (pintype "unspecified"))
      (node (ref "R21") (pin "1") (pinfunction "1_1") (pintype "input"))
      (node (ref "U7") (pin "7") (pinfunction "HO_7") (pintype "unspecified"))
    )
    (net (code "45") (name "Net-(D7-A)") (class "Default")
      (node (ref "D7") (pin "2") (pinfunction "A_2") (pintype "unspecified"))
      (node (ref "Q2") (pin "4") (pinfunction "G_4") (pintype "unspecified"))
      (node (ref "R22") (pin "2") (pinfunction "2_2") (pintype "input"))
      (node (ref "R28") (pin "1") (pinfunction "1_1") (pintype "input"))
    )
    (net (code "46") (name "Net-(D7-K)") (class "Default")
      (node (ref "D7") (pin "1") (pinfunction "K_1") (pintype "unspecified"))
      (node (ref "R22") (pin "1") (pinfunction "1_1") (pintype "input"))
      (node (ref "U7") (pin "5") (pinfunction "LO_5") (pintype "unspecified"))
    )
    (net (code "47") (name "Net-(D8-A)") (class "Default")
      (node (ref "D8") (pin "2") (pinfunction "A_2") (pintype "unspecified"))
      (node (ref "Q3") (pin "4") (pinfunction "G_4") (pintype "unspecified"))
      (node (ref "R23") (pin "2") (pinfunction "2_2") (pintype "input"))
      (node (ref "R29") (pin "2") (pinfunction "2_2") (pintype "input"))
    )
    (net (code "48") (name "Net-(D8-K)") (class "Default")
      (node (ref "D8") (pin "1") (pinfunction "K_1") (pintype "unspecified"))
      (node (ref "R23") (pin "1") (pinfunction "1_1") (pintype "input"))
      (node (ref "U8") (pin "7") (pinfunction "HO_7") (pintype "unspecified"))
    )
    (net (code "49") (name "Net-(D9-A)") (class "Default")
      (node (ref "D9") (pin "2") (pinfunction "A_2") (pintype "unspecified"))
      (node (ref "Q4") (pin "4") (pinfunction "G_4") (pintype "unspecified"))
      (node (ref "R24") (pin "2") (pinfunction "2_2") (pintype "input"))
      (node (ref "R30") (pin "1") (pinfunction "1_1") (pintype "input"))
    )
    (net (code "50") (name "Net-(D9-K)") (class "Default")
      (node (ref "D9") (pin "1") (pinfunction "K_1") (pintype "unspecified"))
      (node (ref "R24") (pin "1") (pinfunction "1_1") (pintype "input"))
      (node (ref "U8") (pin "5") (pinfunction "LO_5") (pintype "unspecified"))
    )
    (net (code "51") (name "Net-(D10-A)") (class "Default")
      (node (ref "D10") (pin "2") (pinfunction "A_2") (pintype "unspecified"))
      (node (ref "Q5") (pin "4") (pinfunction "G_4") (pintype "unspecified"))
      (node (ref "R25") (pin "2") (pinfunction "2_2") (pintype "input"))
      (node (ref "R31") (pin "2") (pinfunction "2_2") (pintype "input"))
    )
    (net (code "52") (name "Net-(D10-K)") (class "Default")
      (node (ref "D10") (pin "1") (pinfunction "K_1") (pintype "unspecified"))
      (node (ref "R25") (pin "1") (pinfunction "1_1") (pintype "input"))
      (node (ref "U9") (pin "7") (pinfunction "HO_7") (pintype "unspecified"))
    )
    (net (code "53") (name "Net-(D11-A)") (class "Default")
      (node (ref "D11") (pin "2") (pinfunction "A_2") (pintype "unspecified"))
      (node (ref "Q6") (pin "4") (pinfunction "G_4") (pintype "unspecified"))
      (node (ref "R26") (pin "2") (pinfunction "2_2") (pintype "input"))
      (node (ref "R32") (pin "1") (pinfunction "1_1") (pintype "input"))
    )
    (net (code "54") (name "Net-(D11-K)") (class "Default")
      (node (ref "D11") (pin "1") (pinfunction "K_1") (pintype "unspecified"))
      (node (ref "R26") (pin "1") (pinfunction "1_1") (pintype "input"))
      (node (ref "U9") (pin "5") (pinfunction "LO_5") (pintype "unspecified"))
    )
    (net (code "55") (name "Net-(LDO1-VOUT)") (class "Default")
      (node (ref "C18") (pin "2") (pinfunction "2_2") (pintype "unspecified"))
      (node (ref "C21") (pin "2") (pinfunction "2_2") (pintype "unspecified"))
      (node (ref "F1") (pin "1") (pinfunction "1_1") (pintype "unspecified"))
      (node (ref "LDO1") (pin "5") (pinfunction "VOUT_5") (pintype "unspecified"))
    )
    (net (code "56") (name "Net-(LED1-+)") (class "Default")
      (node (ref "LED1") (pin "1") (pinfunction "+_1") (pintype "unspecified"))
      (node (ref "R5") (pin "1") (pinfunction "1_1") (pintype "input"))
    )
    (net (code "57") (name "Net-(LED2-+)") (class "Default")
      (node (ref "LED2") (pin "1") (pinfunction "+_1") (pintype "unspecified"))
      (node (ref "R6") (pin "1") (pinfunction "1_1") (pintype "input"))
    )
    (net (code "58") (name "Net-(LED3-A-Pad2)") (class "Default")
      (node (ref "LED3") (pin "2") (pinfunction "A_2") (pintype "unspecified"))
      (node (ref "R8") (pin "1") (pinfunction "1_1") (pintype "input"))
    )
    (net (code "59") (name "Net-(LED3-A-Pad3)") (class "Default")
      (node (ref "LED3") (pin "3") (pinfunction "A_3") (pintype "unspecified"))
      (node (ref "R7") (pin "1") (pinfunction "1_1") (pintype "input"))
    )
    (net (code "60") (name "Net-(LED3-K)") (class "Default")
      (node (ref "LED3") (pin "4") (pinfunction "K_4") (pintype "unspecified"))
      (node (ref "R9") (pin "1") (pinfunction "1_1") (pintype "input"))
    )
    (net (code "61") (name "Net-(R2-Pad2)") (class "Default")
      (node (ref "R2") (pin "2") (pinfunction "2_2") (pintype "input"))
      (node (ref "U1") (pin "3") (pinfunction "3_3") (pintype "unspecified"))
    )
    (net (code "62") (name "Net-(R3-Pad1)") (class "Default")
      (node (ref "R3") (pin "1") (pinfunction "1_1") (pintype "input"))
      (node (ref "U1") (pin "4") (pinfunction "4_4") (pintype "unspecified"))
    )
    (net (code "63") (name "Net-(U3-PGO)") (class "Default")
      (node (ref "R4") (pin "1") (pinfunction "1_1") (pintype "input"))
      (node (ref "U3") (pin "5") (pinfunction "PGO_5") (pintype "unspecified"))
    )
    (net (code "64") (name "Net-(U3-SCL)") (class "Default")
      (node (ref "CN1") (pin "3") (pinfunction "3_3") (pintype "unspecified"))
      (node (ref "CN2") (pin "2") (pinfunction "2_2") (pintype "unspecified"))
      (node (ref "U3") (pin "7") (pinfunction "SCL_7") (pintype "unspecified"))
    )
    (net (code "65") (name "Net-(U3-SDA)") (class "Default")
      (node (ref "CN1") (pin "4") (pinfunction "4_4") (pintype "unspecified"))
      (node (ref "CN2") (pin "1") (pinfunction "1_1") (pintype "unspecified"))
      (node (ref "U3") (pin "6") (pinfunction "SDA_6") (pintype "unspecified"))
    )
    (net (code "66") (name "Net-(U3-VDD3V3)") (class "Default")
      (node (ref "C6") (pin "2") (pinfunction "2_2") (pintype "unspecified"))
      (node (ref "CN1") (pin "1") (pinfunction "1_1") (pintype "unspecified"))
      (node (ref "CN2") (pin "4") (pinfunction "4_4") (pintype "unspecified"))
      (node (ref "U3") (pin "1") (pinfunction "VDD5V_1") (pintype "unspecified"))
      (node (ref "U3") (pin "2") (pinfunction "VDD3V3_2") (pintype "unspecified"))
    )
    (net (code "67") (name "Net-(U5-UD+)") (class "Default")
      (node (ref "U5") (pin "1") (pinfunction "UD+_1") (pintype "unspecified"))
      (node (ref "USB1") (pin "3") (pinfunction "D+_3") (pintype "unspecified"))
    )
    (net (code "68") (name "Net-(U5-UD-)") (class "Default")
      (node (ref "U5") (pin "2") (pinfunction "UD-_2") (pintype "unspecified"))
      (node (ref "USB1") (pin "2") (pinfunction "D-_2") (pintype "unspecified"))
    )
    (net (code "69") (name "Net-(U5-V3)") (class "Default")
      (node (ref "C7") (pin "1") (pinfunction "1_1") (pintype "unspecified"))
      (node (ref "U5") (pin "8") (pinfunction "V3_8") (pintype "unspecified"))
    )
    (net (code "70") (name "Net-(U6-BST)") (class "Default")
      (node (ref "C20") (pin "2") (pinfunction "2_2") (pintype "input"))
      (node (ref "U6") (pin "1") (pinfunction "BST_1") (pintype "unspecified"))
    )
    (net (code "71") (name "Net-(U6-EN)") (class "Default")
      (node (ref "R14") (pin "1") (pinfunction "1_1") (pintype "input"))
      (node (ref "U6") (pin "4") (pinfunction "EN_4") (pintype "unspecified"))
    )
    (net (code "72") (name "Net-(U6-FB)") (class "Default")
      (node (ref "C15") (pin "1") (pinfunction "1_1") (pintype "input"))
      (node (ref "R12") (pin "2") (pinfunction "2_2") (pintype "input"))
      (node (ref "R13") (pin "1") (pinfunction "1_1") (pintype "input"))
      (node (ref "U6") (pin "3") (pinfunction "FB_3") (pintype "unspecified"))
    )
    (net (code "73") (name "Net-(U6-VIN)") (class "Default")
      (node (ref "C10") (pin "1") (pinfunction "1_1") (pintype "input"))
      (node (ref "R14") (pin "2") (pinfunction "2_2") (pintype "input"))
      (node (ref "SW2") (pin "3") (pinfunction "3_3") (pintype "unspecified"))
      (node (ref "U6") (pin "5") (pinfunction "VIN_5") (pintype "unspecified"))
    )
    (net (code "74") (name "Net-(U7-HIN)") (class "Default")
      (node (ref "R15") (pin "2") (pinfunction "2_2") (pintype "input"))
      (node (ref "U7") (pin "2") (pinfunction "HIN_2") (pintype "unspecified"))
    )
    (net (code "75") (name "Net-(U7-LIN)") (class "Default")
      (node (ref "R16") (pin "2") (pinfunction "2_2") (pintype "input"))
      (node (ref "U7") (pin "3") (pinfunction "LIN_3") (pintype "unspecified"))
    )
    (net (code "76") (name "Net-(U7-VS)") (class "Default")
      (node (ref "C23") (pin "2") (pinfunction "2_2") (pintype "unspecified"))
      (node (ref "Q1") (pin "1") (pinfunction "S_1") (pintype "unspecified"))
      (node (ref "Q1") (pin "2") (pinfunction "S_2") (pintype "unspecified"))
      (node (ref "Q1") (pin "3") (pinfunction "S_3") (pintype "unspecified"))
      (node (ref "Q2") (pin "5") (pinfunction "D_5") (pintype "unspecified"))
      (node (ref "Q2") (pin "6") (pinfunction "D_6") (pintype "unspecified"))
      (node (ref "Q2") (pin "7") (pinfunction "D_7") (pintype "unspecified"))
      (node (ref "Q2") (pin "8") (pinfunction "D_8") (pintype "unspecified"))
      (node (ref "R27") (pin "1") (pinfunction "1_1") (pintype "input"))
      (node (ref "U10") (pin "1") (pinfunction "IP+_1") (pintype "unspecified"))
      (node (ref "U10") (pin "2") (pinfunction "IP+_2") (pintype "unspecified"))
      (node (ref "U7") (pin "6") (pinfunction "VS_6") (pintype "unspecified"))
    )
    (net (code "77") (name "Net-(U8-HIN)") (class "Default")
      (node (ref "R17") (pin "2") (pinfunction "2_2") (pintype "input"))
      (node (ref "U8") (pin "2") (pinfunction "HIN_2") (pintype "unspecified"))
    )
    (net (code "78") (name "Net-(U8-LIN)") (class "Default")
      (node (ref "R18") (pin "2") (pinfunction "2_2") (pintype "input"))
      (node (ref "U8") (pin "3") (pinfunction "LIN_3") (pintype "unspecified"))
    )
    (net (code "79") (name "Net-(U8-VS)") (class "Default")
      (node (ref "C24") (pin "2") (pinfunction "2_2") (pintype "unspecified"))
      (node (ref "Q3") (pin "1") (pinfunction "S_1") (pintype "unspecified"))
      (node (ref "Q3") (pin "2") (pinfunction "S_2") (pintype "unspecified"))
      (node (ref "Q3") (pin "3") (pinfunction "S_3") (pintype "unspecified"))
      (node (ref "Q4") (pin "5") (pinfunction "D_5") (pintype "unspecified"))
      (node (ref "Q4") (pin "6") (pinfunction "D_6") (pintype "unspecified"))
      (node (ref "Q4") (pin "7") (pinfunction "D_7") (pintype "unspecified"))
      (node (ref "Q4") (pin "8") (pinfunction "D_8") (pintype "unspecified"))
      (node (ref "R29") (pin "1") (pinfunction "1_1") (pintype "input"))
      (node (ref "U11") (pin "1") (pinfunction "IP+_1") (pintype "unspecified"))
      (node (ref "U11") (pin "2") (pinfunction "IP+_2") (pintype "unspecified"))
      (node (ref "U8") (pin "6") (pinfunction "VS_6") (pintype "unspecified"))
    )
    (net (code "80") (name "Net-(U9-HIN)") (class "Default")
      (node (ref "R19") (pin "2") (pinfunction "2_2") (pintype "input"))
      (node (ref "U9") (pin "2") (pinfunction "HIN_2") (pintype "unspecified"))
    )
    (net (code "81") (name "Net-(U9-LIN)") (class "Default")
      (node (ref "R20") (pin "2") (pinfunction "2_2") (pintype "input"))
      (node (ref "U9") (pin "3") (pinfunction "LIN_3") (pintype "unspecified"))
    )
    (net (code "82") (name "Net-(U9-VS)") (class "Default")
      (node (ref "C25") (pin "2") (pinfunction "2_2") (pintype "unspecified"))
      (node (ref "Q5") (pin "1") (pinfunction "S_1") (pintype "unspecified"))
      (node (ref "Q5") (pin "2") (pinfunction "S_2") (pintype "unspecified"))
      (node (ref "Q5") (pin "3") (pinfunction "S_3") (pintype "unspecified"))
      (node (ref "Q6") (pin "5") (pinfunction "D_5") (pintype "unspecified"))
      (node (ref "Q6") (pin "6") (pinfunction "D_6") (pintype "unspecified"))
      (node (ref "Q6") (pin "7") (pinfunction "D_7") (pintype "unspecified"))
      (node (ref "Q6") (pin "8") (pinfunction "D_8") (pintype "unspecified"))
      (node (ref "R31") (pin "1") (pinfunction "1_1") (pintype "input"))
      (node (ref "U12") (pin "1") (pinfunction "IP+_1") (pintype "unspecified"))
      (node (ref "U12") (pin "2") (pinfunction "IP+_2") (pintype "unspecified"))
      (node (ref "U9") (pin "6") (pinfunction "VS_6") (pintype "unspecified"))
    )
    (net (code "83") (name "Net-(U10-VOUT)") (class "Default")
      (node (ref "R33") (pin "1") (pinfunction "1_1") (pintype "input"))
      (node (ref "U10") (pin "7") (pinfunction "VOUT_7") (pintype "unspecified"))
    )
    (net (code "84") (name "Net-(U10-VREF)") (class "Default")
      (node (ref "C29") (pin "1") (pinfunction "1_1") (pintype "unspecified"))
      (node (ref "U10") (pin "6") (pinfunction "VREF_6") (pintype "unspecified"))
    )
    (net (code "85") (name "Net-(U11-VOUT)") (class "Default")
      (node (ref "R35") (pin "1") (pinfunction "1_1") (pintype "input"))
      (node (ref "U11") (pin "7") (pinfunction "VOUT_7") (pintype "unspecified"))
    )
    (net (code "86") (name "Net-(U11-VREF)") (class "Default")
      (node (ref "C30") (pin "1") (pinfunction "1_1") (pintype "unspecified"))
      (node (ref "U11") (pin "6") (pinfunction "VREF_6") (pintype "unspecified"))
    )
    (net (code "87") (name "Net-(U12-VOUT)") (class "Default")
      (node (ref "R34") (pin "1") (pinfunction "1_1") (pintype "input"))
      (node (ref "U12") (pin "7") (pinfunction "VOUT_7") (pintype "unspecified"))
    )
    (net (code "88") (name "Net-(U12-VREF)") (class "Default")
      (node (ref "C31") (pin "1") (pinfunction "1_1") (pintype "unspecified"))
      (node (ref "U12") (pin "6") (pinfunction "VREF_6") (pintype "unspecified"))
    )
    (net (code "89") (name "VCC") (class "Default")
      (node (ref "R1") (pin "2") (pinfunction "2_2") (pintype "input"))
    )
    (net (code "90") (name "unconnected-(LDO1-NC-Pad4)") (class "Default")
      (node (ref "LDO1") (pin "4") (pinfunction "NC_4") (pintype "unspecified+no_connect"))
    )
    (net (code "91") (name "unconnected-(SW2-Pad1)") (class "Default")
      (node (ref "SW2") (pin "1") (pinfunction "1_1") (pintype "unspecified"))
    )
    (net (code "92") (name "unconnected-(SW2-Pad4)") (class "Default")
      (node (ref "SW2") (pin "4") (pinfunction "4_4") (pintype "unspecified"))
    )
    (net (code "93") (name "unconnected-(SW2-Pad5)") (class "Default")
      (node (ref "SW2") (pin "5") (pinfunction "5_5") (pintype "unspecified"))
    )
    (net (code "94") (name "unconnected-(U4-PA0-WKUP-Pad10)") (class "Default")
      (node (ref "U4") (pin "10") (pinfunction "PA0-WKUP_10") (pintype "unspecified"))
    )
    (net (code "95") (name "unconnected-(U4-PA1-Pad11)") (class "Default")
      (node (ref "U4") (pin "11") (pinfunction "PA1_11") (pintype "unspecified"))
    )
    (net (code "96") (name "unconnected-(U4-PA4-Pad14)") (class "Default")
      (node (ref "U4") (pin "14") (pinfunction "PA4_14") (pintype "unspecified"))
    )
    (net (code "97") (name "unconnected-(U4-PA5-Pad15)") (class "Default")
      (node (ref "U4") (pin "15") (pinfunction "PA5_15") (pintype "unspecified"))
    )
    (net (code "98") (name "unconnected-(U4-PA15-Pad38)") (class "Default")
      (node (ref "U4") (pin "38") (pinfunction "PA15_38") (pintype "unspecified"))
    )
    (net (code "99") (name "unconnected-(U4-PB1-Pad19)") (class "Default")
      (node (ref "U4") (pin "19") (pinfunction "PB1_19") (pintype "unspecified"))
    )
    (net (code "100") (name "unconnected-(U4-PB12-Pad25)") (class "Default")
      (node (ref "U4") (pin "25") (pinfunction "PB12_25") (pintype "unspecified"))
    )
    (net (code "101") (name "unconnected-(U4-PC13-TAMPER-RTC-Pad2)") (class "Default")
      (node (ref "U4") (pin "2") (pinfunction "PC13-TAMPER-RTC_2") (pintype "unspecified"))
    )
    (net (code "102") (name "unconnected-(U5-RTS#-Pad4)") (class "Default")
      (node (ref "U5") (pin "4") (pinfunction "RTS#_4") (pintype "unspecified"))
    )
    (net (code "103") (name "unconnected-(USB1-ID-Pad4)") (class "Default")
      (node (ref "USB1") (pin "4") (pinfunction "ID_4") (pintype "unspecified"))
    )
    (net (code "104") (name "unconnected-(USB2-ID-Pad4)") (class "Default")
      (node (ref "USB2") (pin "4") (pinfunction "ID_4") (pintype "unspecified"))
    )
  )
)
